# power.net
KiCad netlist of a schematic drawn in Altium Designer
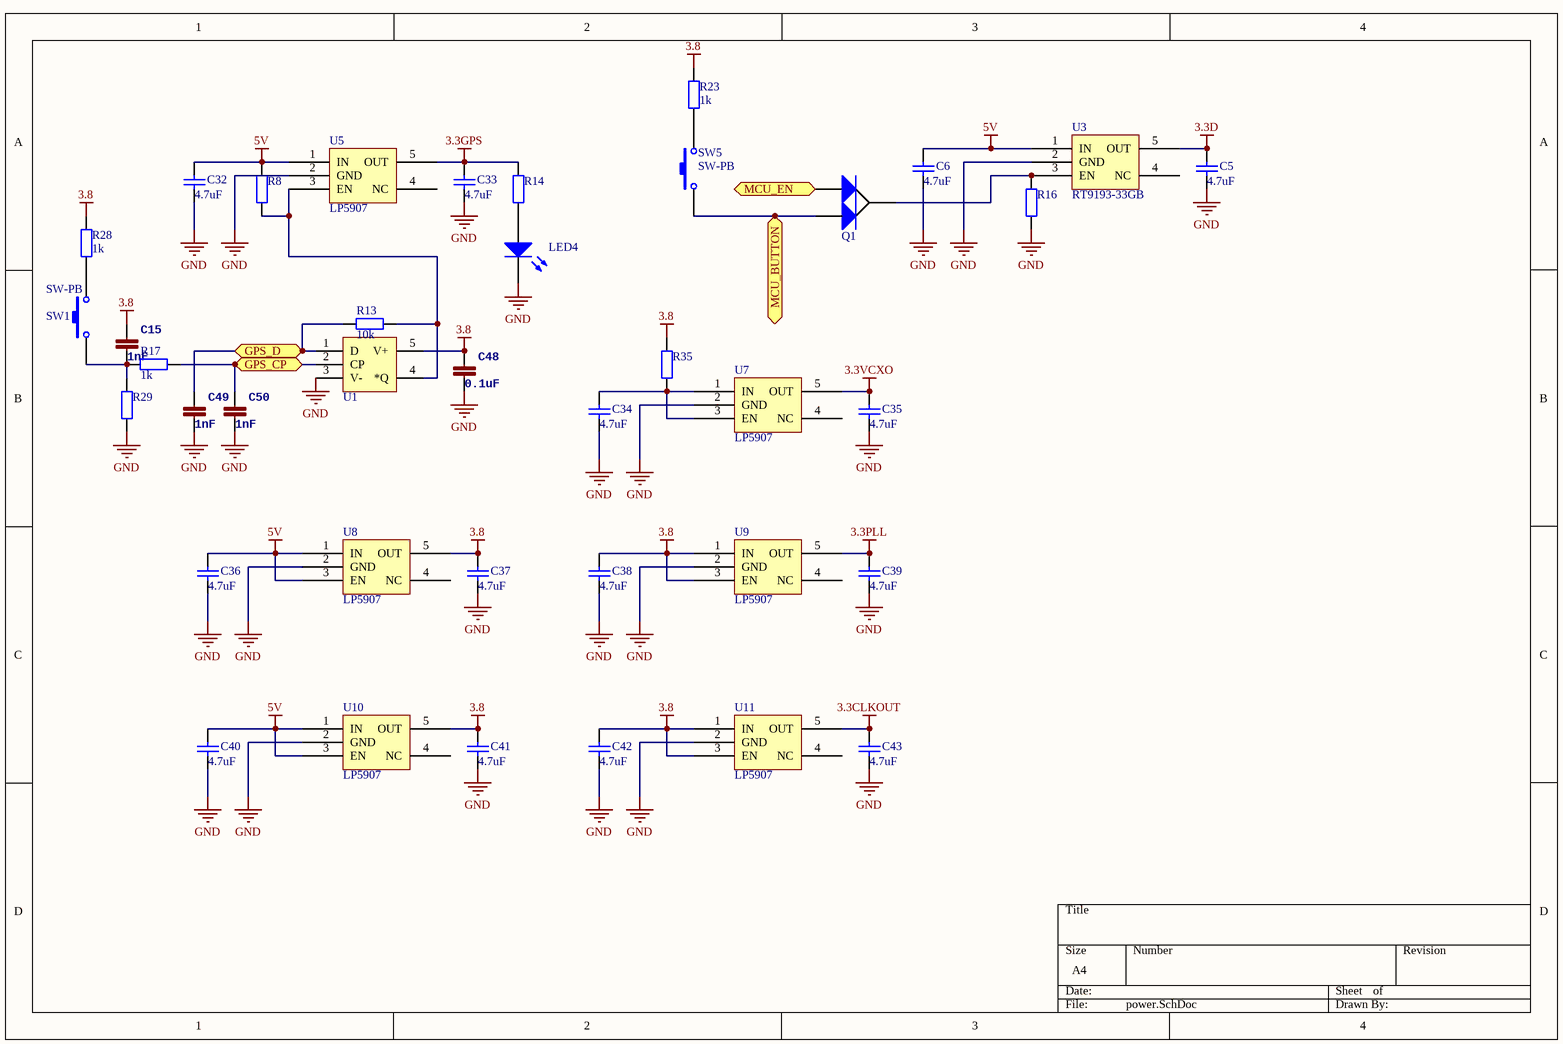
[diagram p0: power.SchDoc]

(export (version "E")
  (design (tool "Eeschema 10.0.6"))
  (components
    (comp (ref "C5")
      (value "4.7uF")
      (footprint "0603L")
      (description "Capacitor")
      (fields (field (name "PUBLISHER") "Altium Limited"))
      (libsource (lib "RTC6705") (part "Cap"))
    )
    (comp (ref "C6")
      (value "4.7uF")
      (footprint "0603L")
      (description "Capacitor")
      (fields (field (name "PUBLISHER") "Altium Limited"))
      (libsource (lib "RTC6705") (part "Cap"))
    )
    (comp (ref "C15")
      (value "1nF")
      (footprint "0402")
      (description "<b>Capacitor</b>\nStandard 0603 ceramic capacitor, and 0.1\" leaded capacitor.")
      (fields (field (name "PARTNO") "CC0402ZRY5V7BB104"))
      (libsource (lib "pixhawk2") (part "CAP0402-CAP"))
    )
    (comp (ref "C32")
      (value "4.7uF")
      (footprint "0603L")
      (description "Capacitor")
      (fields (field (name "PUBLISHER") "Altium Limited"))
      (libsource (lib "RTC6705") (part "Cap"))
    )
    (comp (ref "C33")
      (value "4.7uF")
      (footprint "0603L")
      (description "Capacitor")
      (fields (field (name "PUBLISHER") "Altium Limited"))
      (libsource (lib "RTC6705") (part "Cap"))
    )
    (comp (ref "C34")
      (value "4.7uF")
      (footprint "0603L")
      (description "Capacitor")
      (fields (field (name "PUBLISHER") "Altium Limited"))
      (libsource (lib "RTC6705") (part "Cap"))
    )
    (comp (ref "C35")
      (value "4.7uF")
      (footprint "0603L")
      (description "Capacitor")
      (fields (field (name "PUBLISHER") "Altium Limited"))
      (libsource (lib "RTC6705") (part "Cap"))
    )
    (comp (ref "C36")
      (value "4.7uF")
      (footprint "0603L")
      (description "Capacitor")
      (fields (field (name "PUBLISHER") "Altium Limited"))
      (libsource (lib "RTC6705") (part "Cap"))
    )
    (comp (ref "C37")
      (value "4.7uF")
      (footprint "0603L")
      (description "Capacitor")
      (fields (field (name "PUBLISHER") "Altium Limited"))
      (libsource (lib "RTC6705") (part "Cap"))
    )
    (comp (ref "C38")
      (value "4.7uF")
      (footprint "0603L")
      (description "Capacitor")
      (fields (field (name "PUBLISHER") "Altium Limited"))
      (libsource (lib "RTC6705") (part "Cap"))
    )
    (comp (ref "C39")
      (value "4.7uF")
      (footprint "0603L")
      (description "Capacitor")
      (fields (field (name "PUBLISHER") "Altium Limited"))
      (libsource (lib "RTC6705") (part "Cap"))
    )
    (comp (ref "C40")
      (value "4.7uF")
      (footprint "0603L")
      (description "Capacitor")
      (fields (field (name "PUBLISHER") "Altium Limited"))
      (libsource (lib "RTC6705") (part "Cap"))
    )
    (comp (ref "C41")
      (value "4.7uF")
      (footprint "0603L")
      (description "Capacitor")
      (fields (field (name "PUBLISHER") "Altium Limited"))
      (libsource (lib "RTC6705") (part "Cap"))
    )
    (comp (ref "C42")
      (value "4.7uF")
      (footprint "0603L")
      (description "Capacitor")
      (fields (field (name "PUBLISHER") "Altium Limited"))
      (libsource (lib "RTC6705") (part "Cap"))
    )
    (comp (ref "C43")
      (value "4.7uF")
      (footprint "0603L")
      (description "Capacitor")
      (fields (field (name "PUBLISHER") "Altium Limited"))
      (libsource (lib "RTC6705") (part "Cap"))
    )
    (comp (ref "C48")
      (value "0.1uF")
      (footprint "0402")
      (description "<b>Capacitor</b>\nStandard 0603 ceramic capacitor, and 0.1\" leaded capacitor.")
      (fields (field (name "PARTNO") "CC0402ZRY5V7BB104"))
      (libsource (lib "pixhawk2") (part "CAP0402-CAP"))
    )
    (comp (ref "C49")
      (value "1nF")
      (footprint "0402")
      (description "<b>Capacitor</b>\nStandard 0603 ceramic capacitor, and 0.1\" leaded capacitor.")
      (fields (field (name "PARTNO") "CC0402ZRY5V7BB104"))
      (libsource (lib "pixhawk2") (part "CAP0402-CAP"))
    )
    (comp (ref "C50")
      (value "1nF")
      (footprint "0402")
      (description "<b>Capacitor</b>\nStandard 0603 ceramic capacitor, and 0.1\" leaded capacitor.")
      (fields (field (name "PARTNO") "CC0402ZRY5V7BB104"))
      (libsource (lib "pixhawk2") (part "CAP0402-CAP"))
    )
    (comp (ref "LED4")
      (value "LED0")
      (footprint "0603L")
      (description "Typical INFRARED GaAs LED")
      (fields (field (name "PUBLISHER") "Altium Limited"))
      (libsource (lib "Miscellaneous Devices") (part "LED0"))
    )
    (comp (ref "Q1") (value "BAT54C") (footprint "SOT-23B_L") (libsource (lib "sch") (part "BAT54C")))
    (comp (ref "R8")
      (value "~")
      (footprint "0402")
      (description "Resistor")
      (fields (field (name "PUBLISHER") "Altium Limited"))
      (libsource (lib "Miscellaneous Devices") (part "Res2"))
    )
    (comp (ref "R13")
      (value "10k")
      (footprint "0402")
      (description "Resistor")
      (fields (field (name "PUBLISHER") "Altium Limited"))
      (libsource (lib "") (part "Res2_1"))
    )
    (comp (ref "R14")
      (value "~")
      (footprint "0402")
      (description "Resistor")
      (fields (field (name "PUBLISHER") "Altium Limited"))
      (libsource (lib "Miscellaneous Devices") (part "Res2"))
    )
    (comp (ref "R16")
      (value "~")
      (footprint "0402")
      (description "Resistor")
      (fields (field (name "PUBLISHER") "Altium Limited"))
      (libsource (lib "Miscellaneous Devices") (part "Res2"))
    )
    (comp (ref "R17")
      (value "1k")
      (footprint "0402")
      (description "Resistor")
      (fields (field (name "PUBLISHER") "Altium Limited"))
      (libsource (lib "") (part "Res2_3"))
    )
    (comp (ref "R23")
      (value "1k")
      (footprint "0402")
      (description "Resistor")
      (fields (field (name "PUBLISHER") "Altium Limited"))
      (libsource (lib "") (part "Res2_2"))
    )
    (comp (ref "R28")
      (value "1k")
      (footprint "0402")
      (description "Resistor")
      (fields (field (name "PUBLISHER") "Altium Limited"))
      (libsource (lib "") (part "Res2_2"))
    )
    (comp (ref "R29")
      (value "~")
      (footprint "0402")
      (description "Resistor")
      (fields (field (name "PUBLISHER") "Altium Limited"))
      (libsource (lib "") (part "Res2_2"))
    )
    (comp (ref "R35")
      (value "~")
      (footprint "0603L")
      (description "Resistor")
      (fields (field (name "PUBLISHER") "Altium Limited"))
      (libsource (lib "Miscellaneous Devices") (part "Res2"))
    )
    (comp (ref "SW1")
      (value "SW-PB")
      (footprint "SW3x4")
      (description "Switch")
      (fields (field (name "PUBLISHER") "Altium Limited"))
      (libsource (lib "Miscellaneous Devices") (part "SW-PB"))
    )
    (comp (ref "SW5")
      (value "SW-PB")
      (footprint "SW3x4")
      (description "Switch")
      (fields (field (name "PUBLISHER") "Altium Limited"))
      (libsource (lib "Miscellaneous Devices") (part "SW-PB"))
    )
    (comp (ref "U1") (value "74-1G80") (footprint "SOT23-5") (libsource (lib "sch") (part "74-1G80")))
    (comp (ref "U3") (value "RT9193-33GB") (footprint "SOT23-5") (libsource (lib "RTC6705") (part "LP5907")))
    (comp (ref "U5") (value "LP5907") (footprint "SOT23-5") (libsource (lib "RTC6705") (part "LP5907")))
    (comp (ref "U7") (value "LP5907") (footprint "SOT23-5") (libsource (lib "RTC6705") (part "LP5907")))
    (comp (ref "U8") (value "LP5907") (footprint "SOT23-5") (libsource (lib "RTC6705") (part "LP5907")))
    (comp (ref "U9") (value "LP5907") (footprint "SOT23-5") (libsource (lib "RTC6705") (part "LP5907")))
    (comp (ref "U10") (value "LP5907") (footprint "SOT23-5") (libsource (lib "RTC6705") (part "LP5907")))
    (comp (ref "U11") (value "LP5907") (footprint "SOT23-5") (libsource (lib "RTC6705") (part "LP5907")))
  )
  (nets
    (net (code "1") (name "/GPS_CP") (class "Default")
      (node (ref "C50") (pin "1") (pinfunction "1_1") (pintype "passive"))
      (node (ref "R17") (pin "1") (pinfunction "1_1") (pintype "passive"))
      (node (ref "U1") (pin "2") (pinfunction "CP_2") (pintype "passive"))
    )
    (net (code "2") (name "/GPS_D") (class "Default")
      (node (ref "C49") (pin "1") (pinfunction "1_1") (pintype "passive"))
      (node (ref "R13") (pin "1") (pinfunction "1_1") (pintype "passive"))
      (node (ref "U1") (pin "1") (pinfunction "D_1") (pintype "passive"))
    )
    (net (code "3") (name "/MCU_BUTTON") (class "Default")
      (node (ref "Q1") (pin "2") (pinfunction "A_2") (pintype "passive"))
      (node (ref "SW5") (pin "1") (pinfunction "1_1") (pintype "passive"))
    )
    (net (code "4") (name "/MCU_EN") (class "Default")
      (node (ref "Q1") (pin "1") (pinfunction "A_1") (pintype "passive"))
    )
    (net (code "5") (name "3.3CLKOUT") (class "Default")
      (node (ref "C43") (pin "2") (pinfunction "2_2") (pintype "passive"))
      (node (ref "U11") (pin "5") (pinfunction "OUT_5") (pintype "passive"))
    )
    (net (code "6") (name "3.3D") (class "Default")
      (node (ref "C5") (pin "2") (pinfunction "2_2") (pintype "passive"))
      (node (ref "U3") (pin "5") (pinfunction "OUT_5") (pintype "passive"))
    )
    (net (code "7") (name "3.3GPS") (class "Default")
      (node (ref "C33") (pin "2") (pinfunction "2_2") (pintype "passive"))
      (node (ref "R14") (pin "1") (pinfunction "1_1") (pintype "passive"))
      (node (ref "U5") (pin "5") (pinfunction "OUT_5") (pintype "passive"))
    )
    (net (code "8") (name "3.3PLL") (class "Default")
      (node (ref "C39") (pin "2") (pinfunction "2_2") (pintype "passive"))
      (node (ref "U9") (pin "5") (pinfunction "OUT_5") (pintype "passive"))
    )
    (net (code "9") (name "3.3VCXO") (class "Default")
      (node (ref "C35") (pin "2") (pinfunction "2_2") (pintype "passive"))
      (node (ref "U7") (pin "5") (pinfunction "OUT_5") (pintype "passive"))
    )
    (net (code "10") (name "3.8") (class "Default")
      (node (ref "C15") (pin "1") (pinfunction "1_1") (pintype "passive"))
      (node (ref "C37") (pin "2") (pinfunction "2_2") (pintype "passive"))
      (node (ref "C38") (pin "2") (pinfunction "2_2") (pintype "passive"))
      (node (ref "C41") (pin "2") (pinfunction "2_2") (pintype "passive"))
      (node (ref "C42") (pin "2") (pinfunction "2_2") (pintype "passive"))
      (node (ref "C48") (pin "1") (pinfunction "1_1") (pintype "passive"))
      (node (ref "R23") (pin "2") (pinfunction "2_2") (pintype "passive"))
      (node (ref "R28") (pin "2") (pinfunction "2_2") (pintype "passive"))
      (node (ref "R35") (pin "1") (pinfunction "1_1") (pintype "passive"))
      (node (ref "U1") (pin "5") (pinfunction "V+_5") (pintype "passive"))
      (node (ref "U10") (pin "5") (pinfunction "OUT_5") (pintype "passive"))
      (node (ref "U11") (pin "1") (pinfunction "IN_1") (pintype "passive"))
      (node (ref "U11") (pin "3") (pinfunction "EN_3") (pintype "passive"))
      (node (ref "U8") (pin "5") (pinfunction "OUT_5") (pintype "passive"))
      (node (ref "U9") (pin "1") (pinfunction "IN_1") (pintype "passive"))
      (node (ref "U9") (pin "3") (pinfunction "EN_3") (pintype "passive"))
    )
    (net (code "11") (name "5V") (class "Default")
      (node (ref "C32") (pin "2") (pinfunction "2_2") (pintype "passive"))
      (node (ref "C36") (pin "2") (pinfunction "2_2") (pintype "passive"))
      (node (ref "C40") (pin "2") (pinfunction "2_2") (pintype "passive"))
      (node (ref "C6") (pin "2") (pinfunction "2_2") (pintype "passive"))
      (node (ref "R8") (pin "1") (pinfunction "1_1") (pintype "passive"))
      (node (ref "U10") (pin "1") (pinfunction "IN_1") (pintype "passive"))
      (node (ref "U10") (pin "3") (pinfunction "EN_3") (pintype "passive"))
      (node (ref "U3") (pin "1") (pinfunction "IN_1") (pintype "passive"))
      (node (ref "U5") (pin "1") (pinfunction "IN_1") (pintype "passive"))
      (node (ref "U8") (pin "1") (pinfunction "IN_1") (pintype "passive"))
      (node (ref "U8") (pin "3") (pinfunction "EN_3") (pintype "passive"))
    )
    (net (code "12") (name "GND") (class "Default")
      (node (ref "C32") (pin "1") (pinfunction "1_1") (pintype "passive"))
      (node (ref "C33") (pin "1") (pinfunction "1_1") (pintype "passive"))
      (node (ref "C34") (pin "1") (pinfunction "1_1") (pintype "passive"))
      (node (ref "C35") (pin "1") (pinfunction "1_1") (pintype "passive"))
      (node (ref "C36") (pin "1") (pinfunction "1_1") (pintype "passive"))
      (node (ref "C37") (pin "1") (pinfunction "1_1") (pintype "passive"))
      (node (ref "C38") (pin "1") (pinfunction "1_1") (pintype "passive"))
      (node (ref "C39") (pin "1") (pinfunction "1_1") (pintype "passive"))
      (node (ref "C40") (pin "1") (pinfunction "1_1") (pintype "passive"))
      (node (ref "C41") (pin "1") (pinfunction "1_1") (pintype "passive"))
      (node (ref "C42") (pin "1") (pinfunction "1_1") (pintype "passive"))
      (node (ref "C43") (pin "1") (pinfunction "1_1") (pintype "passive"))
      (node (ref "C48") (pin "2") (pinfunction "2_2") (pintype "passive"))
      (node (ref "C49") (pin "2") (pinfunction "2_2") (pintype "passive"))
      (node (ref "C5") (pin "1") (pinfunction "1_1") (pintype "passive"))
      (node (ref "C50") (pin "2") (pinfunction "2_2") (pintype "passive"))
      (node (ref "C6") (pin "1") (pinfunction "1_1") (pintype "passive"))
      (node (ref "LED4") (pin "2") (pinfunction "K_2") (pintype "passive"))
      (node (ref "R16") (pin "2") (pinfunction "2_2") (pintype "passive"))
      (node (ref "R29") (pin "1") (pinfunction "1_1") (pintype "passive"))
      (node (ref "U1") (pin "3") (pinfunction "V-_3") (pintype "passive"))
      (node (ref "U10") (pin "2") (pinfunction "GND_2") (pintype "passive"))
      (node (ref "U11") (pin "2") (pinfunction "GND_2") (pintype "passive"))
      (node (ref "U3") (pin "2") (pinfunction "GND_2") (pintype "passive"))
      (node (ref "U5") (pin "2") (pinfunction "GND_2") (pintype "passive"))
      (node (ref "U7") (pin "2") (pinfunction "GND_2") (pintype "passive"))
      (node (ref "U8") (pin "2") (pinfunction "GND_2") (pintype "passive"))
      (node (ref "U9") (pin "2") (pinfunction "GND_2") (pintype "passive"))
    )
    (net (code "13") (name "Net-(C15-Pad2)") (class "Default")
      (node (ref "C15") (pin "2") (pinfunction "2_2") (pintype "passive"))
      (node (ref "R17") (pin "2") (pinfunction "2_2") (pintype "passive"))
      (node (ref "R29") (pin "2") (pinfunction "2_2") (pintype "passive"))
      (node (ref "SW1") (pin "1") (pinfunction "1_1") (pintype "passive"))
    )
    (net (code "14") (name "Net-(LED4-A)") (class "Default")
      (node (ref "LED4") (pin "1") (pinfunction "A_1") (pintype "passive"))
      (node (ref "R14") (pin "2") (pinfunction "2_2") (pintype "passive"))
    )
    (net (code "15") (name "Net-(Q1-K)") (class "Default")
      (node (ref "Q1") (pin "3") (pinfunction "K_3") (pintype "passive"))
      (node (ref "R16") (pin "1") (pinfunction "1_1") (pintype "passive"))
      (node (ref "U3") (pin "3") (pinfunction "EN_3") (pintype "passive"))
    )
    (net (code "16") (name "Net-(R23-Pad1)") (class "Default")
      (node (ref "R23") (pin "1") (pinfunction "1_1") (pintype "passive"))
      (node (ref "SW5") (pin "2") (pinfunction "2_2") (pintype "passive"))
    )
    (net (code "17") (name "Net-(R28-Pad1)") (class "Default")
      (node (ref "R28") (pin "1") (pinfunction "1_1") (pintype "passive"))
      (node (ref "SW1") (pin "2") (pinfunction "2_2") (pintype "passive"))
    )
    (net (code "18") (name "Net-(U1-*Q)") (class "Default")
      (node (ref "R13") (pin "2") (pinfunction "2_2") (pintype "passive"))
      (node (ref "R8") (pin "2") (pinfunction "2_2") (pintype "passive"))
      (node (ref "U1") (pin "4") (pinfunction "*Q_4") (pintype "passive"))
      (node (ref "U5") (pin "3") (pinfunction "EN_3") (pintype "passive"))
    )
    (net (code "19") (name "Net-(U7-EN)") (class "Default")
      (node (ref "C34") (pin "2") (pinfunction "2_2") (pintype "passive"))
      (node (ref "R35") (pin "2") (pinfunction "2_2") (pintype "passive"))
      (node (ref "U7") (pin "1") (pinfunction "IN_1") (pintype "passive"))
      (node (ref "U7") (pin "3") (pinfunction "EN_3") (pintype "passive"))
    )
    (net (code "20") (name "unconnected-(U3-NC-Pad4)") (class "Default")
      (node (ref "U3") (pin "4") (pinfunction "NC_4") (pintype "passive"))
    )
    (net (code "21") (name "unconnected-(U5-NC-Pad4)") (class "Default")
      (node (ref "U5") (pin "4") (pinfunction "NC_4") (pintype "passive"))
    )
    (net (code "22") (name "unconnected-(U7-NC-Pad4)") (class "Default")
      (node (ref "U7") (pin "4") (pinfunction "NC_4") (pintype "passive"))
    )
    (net (code "23") (name "unconnected-(U8-NC-Pad4)") (class "Default")
      (node (ref "U8") (pin "4") (pinfunction "NC_4") (pintype "passive"))
    )
    (net (code "24") (name "unconnected-(U9-NC-Pad4)") (class "Default")
      (node (ref "U9") (pin "4") (pinfunction "NC_4") (pintype "passive"))
    )
    (net (code "25") (name "unconnected-(U10-NC-Pad4)") (class "Default")
      (node (ref "U10") (pin "4") (pinfunction "NC_4") (pintype "passive"))
    )
    (net (code "26") (name "unconnected-(U11-NC-Pad4)") (class "Default")
      (node (ref "U11") (pin "4") (pinfunction "NC_4") (pintype "passive"))
    )
  )
)
